# 1_2_0_XBee_module.net
KiCad netlist of a schematic drawn in Altium Designer
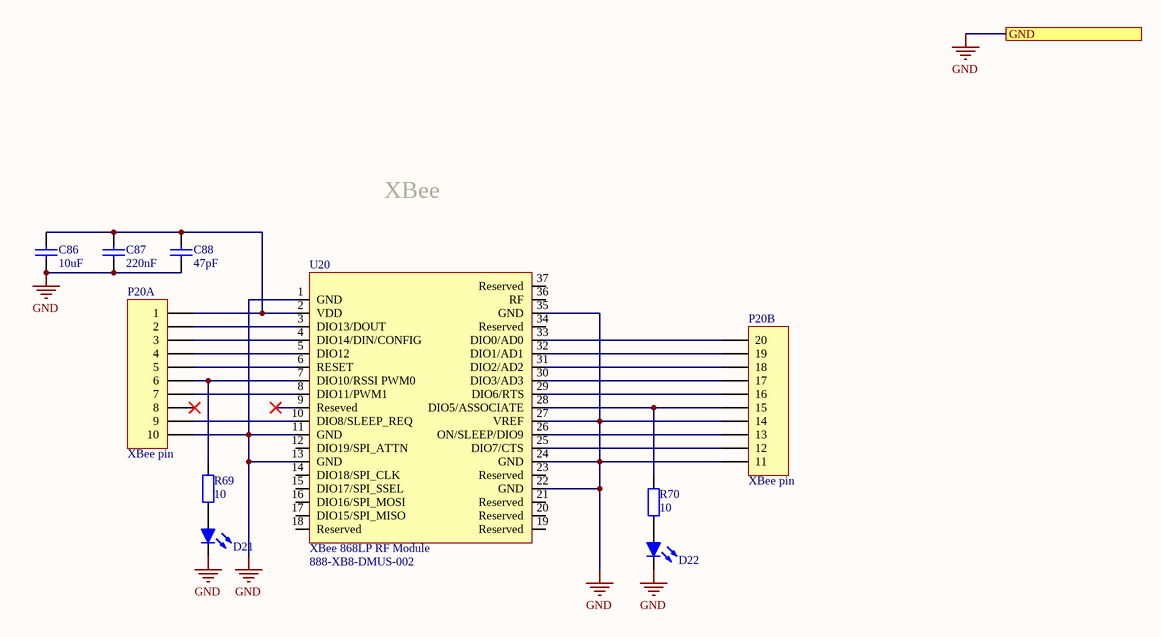
[diagram p0: 1.2.0_XBee_module.SchDoc]

(export (version "E")
  (design (tool "Eeschema 10.0.6"))
  (components
    (comp (ref "C86")
      (value "10uF")
      (footprint "CAP0805W")
      (description "Capacitor")
      (libsource (lib "Rocket_library") (part "C_10uF_16v"))
    )
    (comp (ref "C87")
      (value "220nF")
      (footprint "CAP0603R")
      (description "Capacitor")
      (libsource (lib "Rocket_library") (part "C_220nF"))
    )
    (comp (ref "C88")
      (value "47pF")
      (footprint "CAP0603R")
      (description "Capacitor")
      (libsource (lib "Rocket_library") (part "C_47pF_25V"))
    )
    (comp (ref "D21")
      (value "LED")
      (footprint "WL-SMCW")
      (description "Standard LEDs - SMD WL-SMCW Waterclr 0603 Green")
      (libsource (lib "Rocket_library") (part "LED_SMD_GREEN_0603"))
    )
    (comp (ref "D22")
      (value "LED")
      (footprint "WL-SMCW")
      (description "Standard LEDs - SMD WL-SMCW Waterclr 0603 Green")
      (libsource (lib "Rocket_library") (part "LED_SMD_GREEN_0603"))
    )
    (comp (ref "P20")
      (value "XBee pin")
      (footprint "XBEE PIN")
      (libsource (lib "Rocket_library") (part "XBee pin"))
    )
    (comp (ref "R69")
      (value "10")
      (footprint "0603")
      (description "0.25W 10Ohm")
      (libsource (lib "Rocket_library") (part "R_0603_025W_10Ohm"))
    )
    (comp (ref "R70")
      (value "10")
      (footprint "0603")
      (description "0.25W 10Ohm")
      (libsource (lib "Rocket_library") (part "R_0603_025W_10Ohm"))
    )
    (comp (ref "U20")
      (value "XBee 868LP RF Module")
      (footprint "XBee 868LP RF Module")
      (fields (field (name "SUPPLIER PART NUMBER 1") "888-XB8-DMUS-002"))
      (libsource (lib "Rocket_library") (part "XBee 868LP RF Module"))
    )
  )
  (nets
    (net (code "1") (name "GND") (class "Default")
      (node (ref "C86") (pin "1") (pinfunction "1_1") (pintype "passive"))
      (node (ref "C87") (pin "1") (pinfunction "1_1") (pintype "passive"))
      (node (ref "C88") (pin "1") (pinfunction "1_1") (pintype "passive"))
      (node (ref "D21") (pin "C") (pinfunction "C_C") (pintype "passive"))
      (node (ref "D22") (pin "C") (pinfunction "C_C") (pintype "passive"))
      (node (ref "P20") (pin "10") (pinfunction "10_10") (pintype "passive"))
      (node (ref "P20") (pin "11") (pinfunction "11_11") (pintype "passive"))
      (node (ref "P20") (pin "14") (pinfunction "14_14") (pintype "passive"))
      (node (ref "U20") (pin "1") (pinfunction "GND_1") (pintype "passive"))
      (node (ref "U20") (pin "11") (pinfunction "GND_11") (pintype "passive"))
      (node (ref "U20") (pin "13") (pinfunction "GND_13") (pintype "passive"))
      (node (ref "U20") (pin "22") (pinfunction "GND_22") (pintype "passive"))
      (node (ref "U20") (pin "24") (pinfunction "GND_24") (pintype "passive"))
      (node (ref "U20") (pin "27") (pinfunction "VREF_27") (pintype "passive"))
      (node (ref "U20") (pin "35") (pinfunction "GND_35") (pintype "passive"))
    )
    (net (code "2") (name "Net-(D21-PadA)") (class "Default")
      (node (ref "D21") (pin "A") (pinfunction "A_A") (pintype "passive"))
      (node (ref "R69") (pin "1") (pinfunction "1_1") (pintype "passive"))
    )
    (net (code "3") (name "Net-(D22-PadA)") (class "Default")
      (node (ref "D22") (pin "A") (pinfunction "A_A") (pintype "passive"))
      (node (ref "R70") (pin "1") (pinfunction "1_1") (pintype "passive"))
    )
    (net (code "4") (name "Net-(U20-DIO0{slash}AD0)") (class "Default")
      (node (ref "P20") (pin "20") (pinfunction "20_20") (pintype "passive"))
      (node (ref "U20") (pin "33") (pinfunction "DIO0/AD0_33") (pintype "passive"))
    )
    (net (code "5") (name "Net-(U20-DIO1{slash}AD1)") (class "Default")
      (node (ref "P20") (pin "19") (pinfunction "19_19") (pintype "passive"))
      (node (ref "U20") (pin "32") (pinfunction "DIO1/AD1_32") (pintype "passive"))
    )
    (net (code "6") (name "Net-(U20-DIO2{slash}AD2)") (class "Default")
      (node (ref "P20") (pin "18") (pinfunction "18_18") (pintype "passive"))
      (node (ref "U20") (pin "31") (pinfunction "DIO2/AD2_31") (pintype "passive"))
    )
    (net (code "7") (name "Net-(U20-DIO3{slash}AD3)") (class "Default")
      (node (ref "P20") (pin "17") (pinfunction "17_17") (pintype "passive"))
      (node (ref "U20") (pin "30") (pinfunction "DIO3/AD3_30") (pintype "passive"))
    )
    (net (code "8") (name "Net-(U20-DIO5{slash}ASSOCIATE)") (class "Default")
      (node (ref "P20") (pin "15") (pinfunction "15_15") (pintype "passive"))
      (node (ref "R70") (pin "2") (pinfunction "2_2") (pintype "passive"))
      (node (ref "U20") (pin "28") (pinfunction "DIO5/ASSOCIATE_28") (pintype "passive"))
    )
    (net (code "9") (name "Net-(U20-DIO6{slash}RTS)") (class "Default")
      (node (ref "P20") (pin "16") (pinfunction "16_16") (pintype "passive"))
      (node (ref "U20") (pin "29") (pinfunction "DIO6/RTS_29") (pintype "passive"))
    )
    (net (code "10") (name "Net-(U20-DIO7{slash}CTS)") (class "Default")
      (node (ref "P20") (pin "12") (pinfunction "12_12") (pintype "passive"))
      (node (ref "U20") (pin "25") (pinfunction "DIO7/CTS_25") (pintype "passive"))
    )
    (net (code "11") (name "Net-(U20-DIO8{slash}SLEEP_REQ)") (class "Default")
      (node (ref "P20") (pin "9") (pinfunction "9_9") (pintype "passive"))
      (node (ref "U20") (pin "10") (pinfunction "DIO8/SLEEP_REQ_10") (pintype "passive"))
    )
    (net (code "12") (name "Net-(U20-DIO10{slash}RSSI_PWM0)") (class "Default")
      (node (ref "P20") (pin "6") (pinfunction "6_6") (pintype "passive"))
      (node (ref "R69") (pin "2") (pinfunction "2_2") (pintype "passive"))
      (node (ref "U20") (pin "7") (pinfunction "DIO10/RSSI_PWM0_7") (pintype "passive"))
    )
    (net (code "13") (name "Net-(U20-DIO11{slash}PWM1)") (class "Default")
      (node (ref "P20") (pin "7") (pinfunction "7_7") (pintype "passive"))
      (node (ref "U20") (pin "8") (pinfunction "DIO11/PWM1_8") (pintype "passive"))
    )
    (net (code "14") (name "Net-(U20-DIO12)") (class "Default")
      (node (ref "P20") (pin "4") (pinfunction "4_4") (pintype "passive"))
      (node (ref "U20") (pin "5") (pinfunction "DIO12_5") (pintype "passive"))
    )
    (net (code "15") (name "Net-(U20-DIO13{slash}DOUT)") (class "Default")
      (node (ref "P20") (pin "2") (pinfunction "2_2") (pintype "passive"))
      (node (ref "U20") (pin "3") (pinfunction "DIO13/DOUT_3") (pintype "passive"))
    )
    (net (code "16") (name "Net-(U20-DIO14{slash}DIN{slash}CONFIG)") (class "Default")
      (node (ref "P20") (pin "3") (pinfunction "3_3") (pintype "passive"))
      (node (ref "U20") (pin "4") (pinfunction "DIO14/DIN/CONFIG_4") (pintype "passive"))
    )
    (net (code "17") (name "Net-(U20-ON{slash}SLEEP{slash}DIO9)") (class "Default")
      (node (ref "P20") (pin "13") (pinfunction "13_13") (pintype "passive"))
      (node (ref "U20") (pin "26") (pinfunction "ON/SLEEP/DIO9_26") (pintype "passive"))
    )
    (net (code "18") (name "Net-(U20-RESET)") (class "Default")
      (node (ref "P20") (pin "5") (pinfunction "5_5") (pintype "passive"))
      (node (ref "U20") (pin "6") (pinfunction "RESET_6") (pintype "passive"))
    )
    (net (code "19") (name "Net-(U20-VDD)") (class "Default")
      (node (ref "C86") (pin "2") (pinfunction "2_2") (pintype "passive"))
      (node (ref "C87") (pin "2") (pinfunction "2_2") (pintype "passive"))
      (node (ref "C88") (pin "2") (pinfunction "2_2") (pintype "passive"))
      (node (ref "P20") (pin "1") (pinfunction "1_1") (pintype "passive"))
      (node (ref "U20") (pin "2") (pinfunction "VDD_2") (pintype "passive"))
    )
    (net (code "20") (name "unconnected-(P20-Pad8)") (class "Default")
      (node (ref "P20") (pin "8") (pinfunction "8_8") (pintype "passive+no_connect"))
    )
    (net (code "21") (name "unconnected-(U20-DIO15{slash}SPI_MISO-Pad17)") (class "Default")
      (node (ref "U20") (pin "17") (pinfunction "DIO15/SPI_MISO_17") (pintype "passive"))
    )
    (net (code "22") (name "unconnected-(U20-DIO16{slash}SPI_MOSI-Pad16)") (class "Default")
      (node (ref "U20") (pin "16") (pinfunction "DIO16/SPI_MOSI_16") (pintype "passive"))
    )
    (net (code "23") (name "unconnected-(U20-DIO17{slash}SPI_SSEL-Pad15)") (class "Default")
      (node (ref "U20") (pin "15") (pinfunction "DIO17/SPI_SSEL_15") (pintype "passive"))
    )
    (net (code "24") (name "unconnected-(U20-DIO18{slash}SPI_CLK-Pad14)") (class "Default")
      (node (ref "U20") (pin "14") (pinfunction "DIO18/SPI_CLK_14") (pintype "passive"))
    )
    (net (code "25") (name "unconnected-(U20-DIO19{slash}SPI_ATTN-Pad12)") (class "Default")
      (node (ref "U20") (pin "12") (pinfunction "DIO19/SPI_ATTN_12") (pintype "passive"))
    )
    (net (code "26") (name "unconnected-(U20-RF-Pad36)") (class "Default")
      (node (ref "U20") (pin "36") (pinfunction "RF_36") (pintype "passive"))
    )
    (net (code "27") (name "unconnected-(U20-Reserved-Pad18)") (class "Default")
      (node (ref "U20") (pin "18") (pinfunction "Reserved_18") (pintype "passive"))
    )
    (net (code "28") (name "unconnected-(U20-Reserved-Pad19)") (class "Default")
      (node (ref "U20") (pin "19") (pinfunction "Reserved_19") (pintype "passive"))
    )
    (net (code "29") (name "unconnected-(U20-Reserved-Pad20)") (class "Default")
      (node (ref "U20") (pin "20") (pinfunction "Reserved_20") (pintype "passive"))
    )
    (net (code "30") (name "unconnected-(U20-Reserved-Pad21)") (class "Default")
      (node (ref "U20") (pin "21") (pinfunction "Reserved_21") (pintype "passive"))
    )
    (net (code "31") (name "unconnected-(U20-Reserved-Pad23)") (class "Default")
      (node (ref "U20") (pin "23") (pinfunction "Reserved_23") (pintype "passive"))
    )
    (net (code "32") (name "unconnected-(U20-Reserved-Pad34)") (class "Default")
      (node (ref "U20") (pin "34") (pinfunction "Reserved_34") (pintype "passive"))
    )
    (net (code "33") (name "unconnected-(U20-Reserved-Pad37)") (class "Default")
      (node (ref "U20") (pin "37") (pinfunction "Reserved_37") (pintype "passive"))
    )
    (net (code "34") (name "unconnected-(U20-Reseved-Pad9)") (class "Default")
      (node (ref "U20") (pin "9") (pinfunction "Reseved_9") (pintype "passive+no_connect"))
    )
  )
)
